# Arduino_NMEA_TestBoard.net
KiCad netlist of a schematic drawn in EAGLE
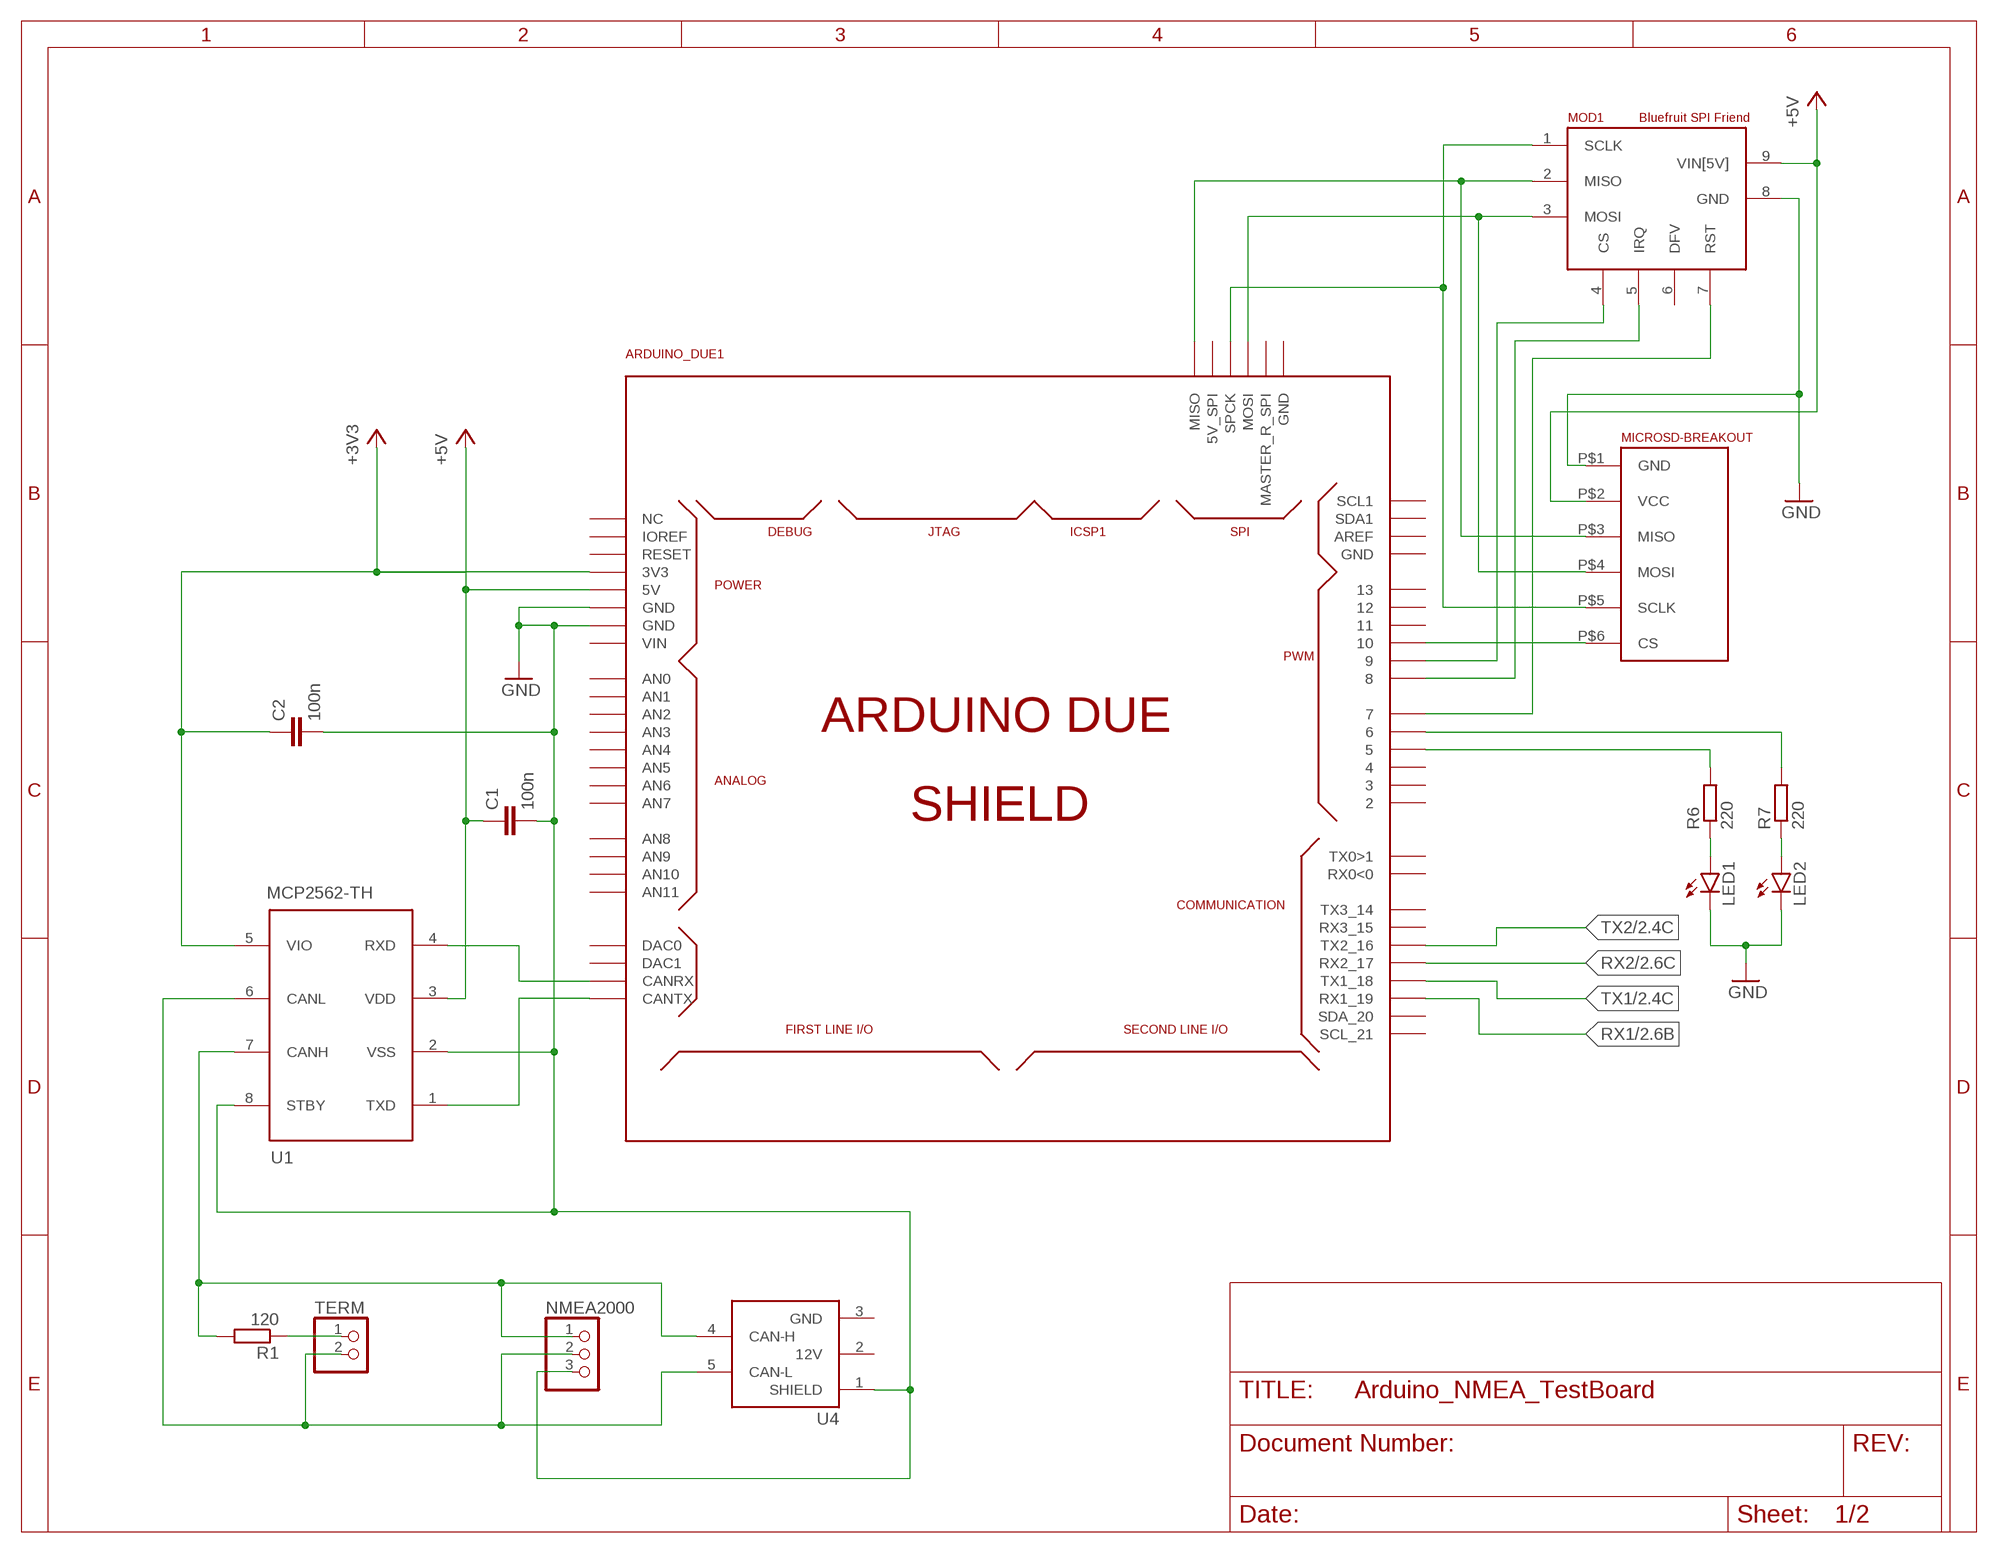
[diagram p0: schematic, sheet 1]
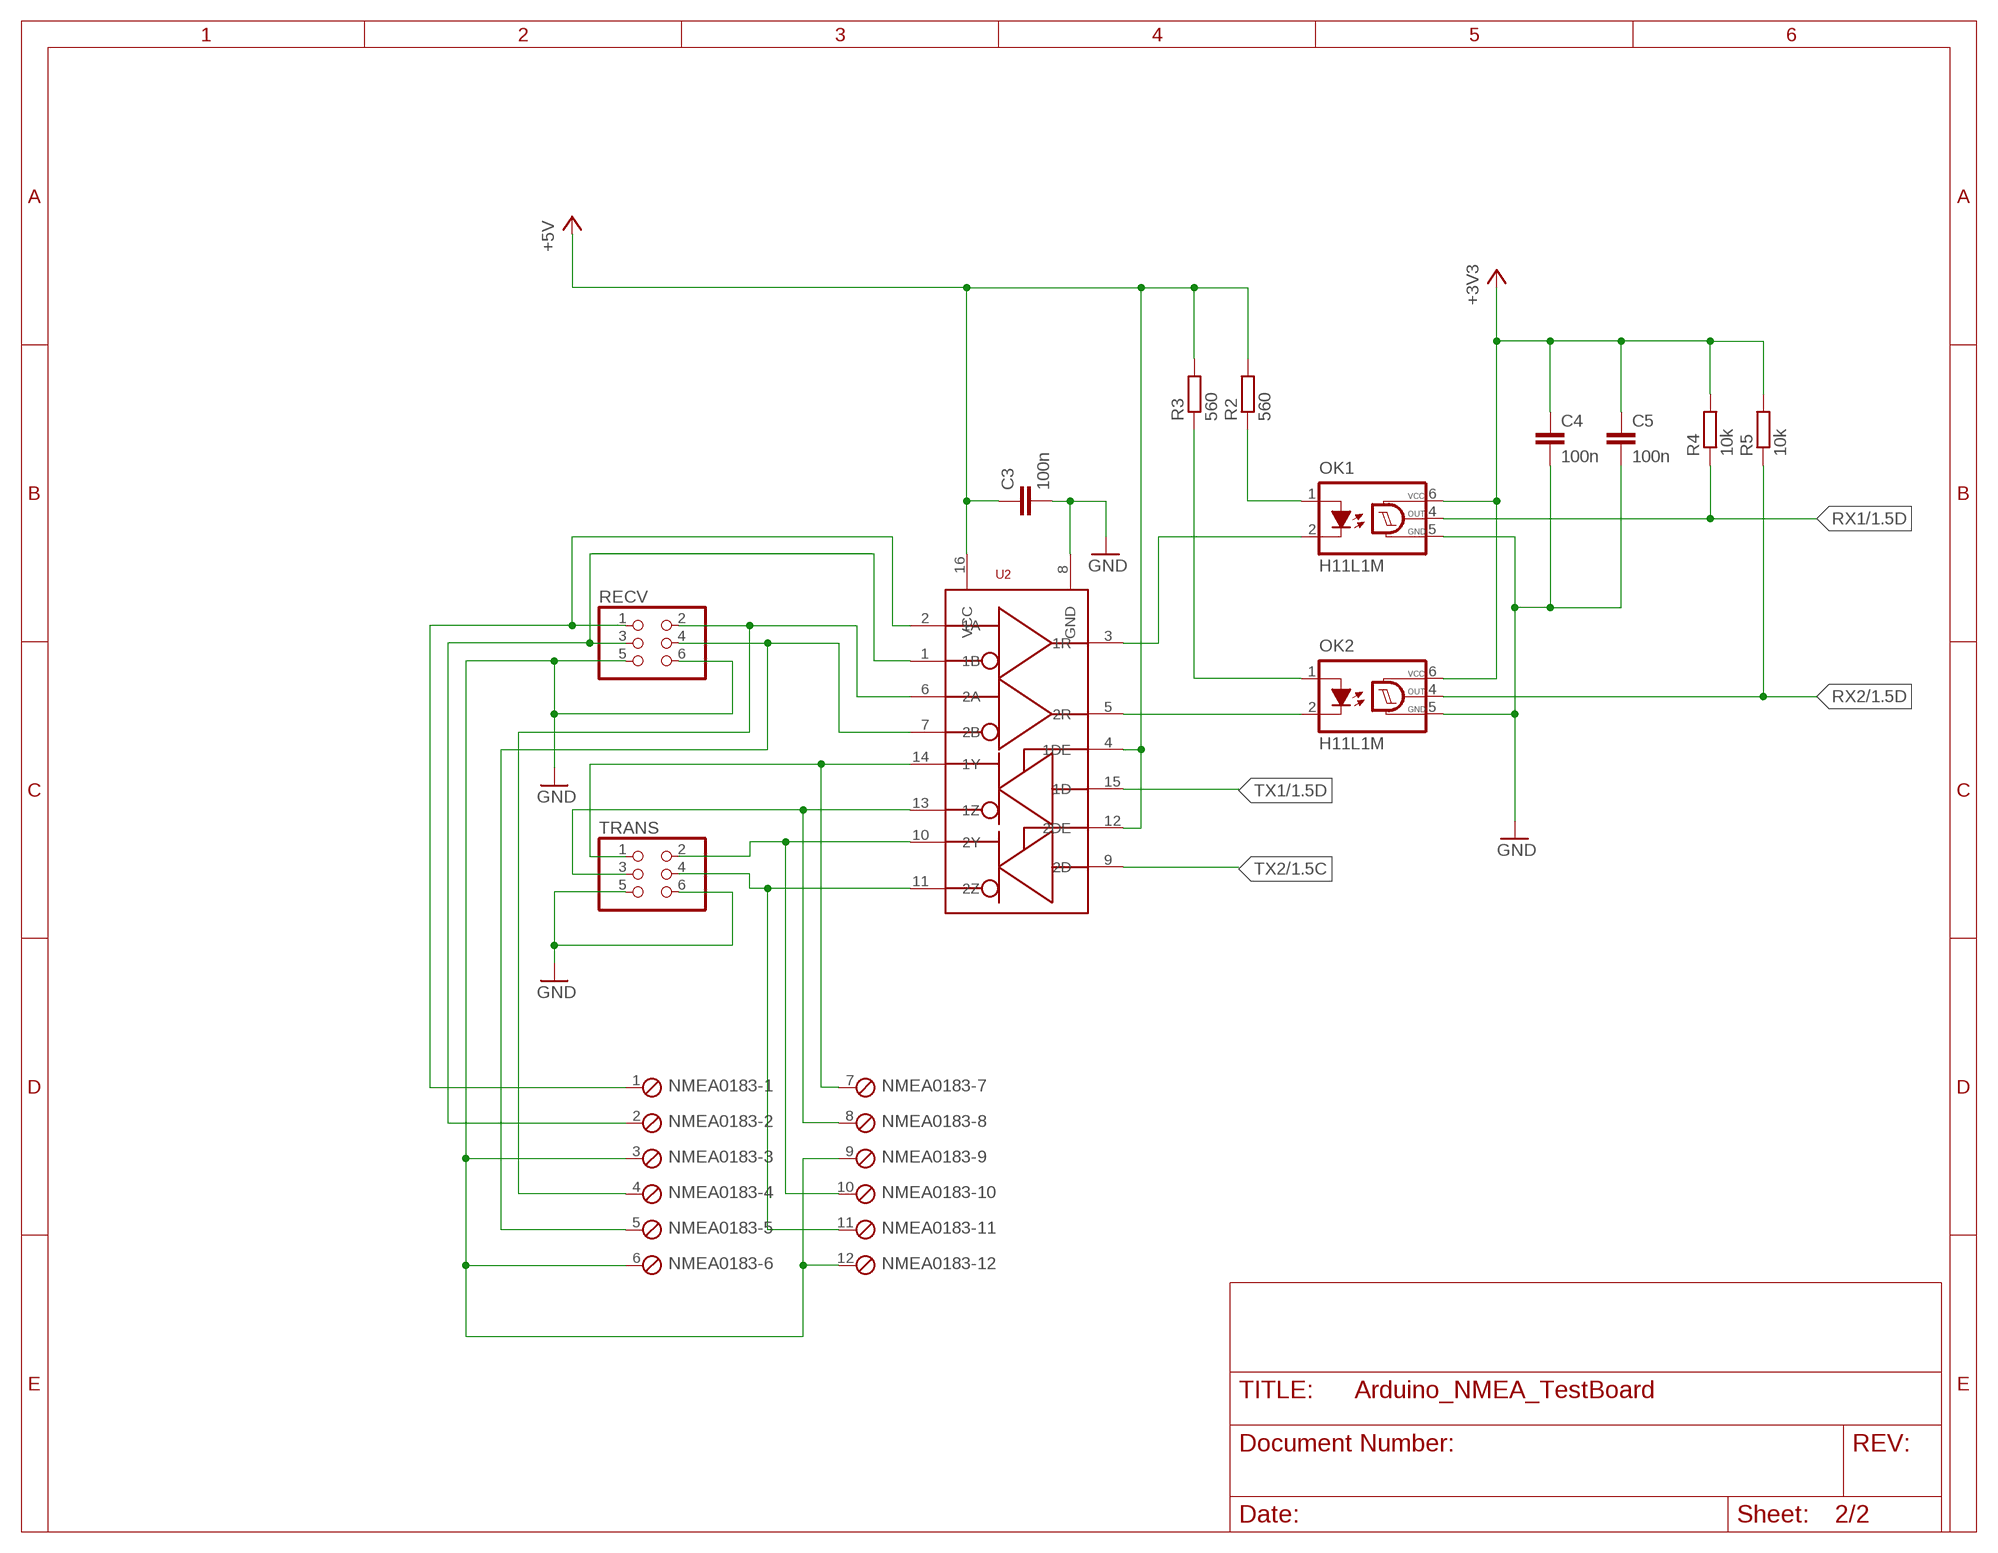
[diagram p1: schematic, sheet 2]

(export (version "E")
  (design (tool "Eeschema 10.0.6"))
  (components
    (comp (ref "C3")
      (value "100n")
      (footprint "eagle-import:C050-025X075")
      (libsource (lib "eagle-import") (part "C-EU050-025X075"))
    )
    (comp (ref "C4")
      (value "100n")
      (footprint "eagle-import:C050-025X075")
      (libsource (lib "eagle-import") (part "C-EU050-025X075"))
    )
    (comp (ref "C5")
      (value "100n")
      (footprint "eagle-import:C050-025X075")
      (libsource (lib "eagle-import") (part "C-EU050-025X075"))
    )
    (comp (ref "NMEA0183")
      (value "MPT12")
      (footprint "eagle-import:12POL254")
      (libsource (lib "eagle-import") (part "MPT12"))
    )
    (comp (ref "OK1")
      (value "H11L1M")
      (footprint "eagle-import:DIL06")
      (fields (field (name "MF") "FAIRCHILD SEMICONDUCTOR") (field (name "MPN") "H11L1-M"))
      (libsource (lib "eagle-import") (part "H11LM1"))
    )
    (comp (ref "OK2")
      (value "H11L1M")
      (footprint "eagle-import:DIL06")
      (fields (field (name "MF") "FAIRCHILD SEMICONDUCTOR") (field (name "MPN") "H11L1-M"))
      (libsource (lib "eagle-import") (part "H11LM1"))
    )
    (comp (ref "R2")
      (value "560")
      (footprint "eagle-import:0207_10")
      (libsource (lib "eagle-import") (part "R-EU_0207/10"))
    )
    (comp (ref "R3")
      (value "560")
      (footprint "eagle-import:0207_10")
      (libsource (lib "eagle-import") (part "R-EU_0207/10"))
    )
    (comp (ref "R4")
      (value "10k")
      (footprint "eagle-import:0207_10")
      (libsource (lib "eagle-import") (part "R-EU_0207/10"))
    )
    (comp (ref "R5")
      (value "10k")
      (footprint "eagle-import:0207_10")
      (libsource (lib "eagle-import") (part "R-EU_0207/10"))
    )
    (comp (ref "RECV")
      (value "PINHD-2X3")
      (footprint "eagle-import:2X03")
      (libsource (lib "eagle-import") (part "PINHD-2X3"))
    )
    (comp (ref "TRANS")
      (value "PINHD-2X3")
      (footprint "eagle-import:2X03")
      (libsource (lib "eagle-import") (part "PINHD-2X3"))
    )
    (comp (ref "U2")
      (value "SN65C1168")
      (footprint "eagle-import:DIP16")
      (libsource (lib "eagle-import") (part "SN65C1168"))
    )
    (comp (ref "ARDUINO_DUE1")
      (value "ARDUINO_DUE_SHIELD")
      (footprint "eagle-import:ARDUINO_DUE_SHIELD")
      (libsource (lib "eagle-import") (part "ARDUINO_DUE_SHIELD"))
    )
    (comp (ref "C1")
      (value "100n")
      (footprint "eagle-import:C050-025X075")
      (libsource (lib "eagle-import") (part "C-EU050-025X075"))
    )
    (comp (ref "C2")
      (value "100n")
      (footprint "eagle-import:C050-025X075")
      (libsource (lib "eagle-import") (part "C-EU050-025X075"))
    )
    (comp (ref "LED1")
      (value "LED5MM")
      (footprint "eagle-import:LED5MM")
      (libsource (lib "eagle-import") (part "LED5MM"))
    )
    (comp (ref "LED2")
      (value "LED5MM")
      (footprint "eagle-import:LED5MM")
      (libsource (lib "eagle-import") (part "LED5MM"))
    )
    (comp (ref "MICROSD-BREAKOUT")
      (value "MICROSD-BREAKOUT")
      (footprint "eagle-import:MICROSD-BREAKOUT")
      (libsource (lib "eagle-import") (part "MICROSD-BREAKOUT"))
    )
    (comp (ref "MOD1")
      (value "BLUEFRUIT-SPI-FRIEND")
      (footprint "eagle-import:BLE_SPIFRIEND")
      (libsource (lib "eagle-import") (part "BLUEFRUIT-SPI-FRIEND"))
    )
    (comp (ref "NMEA2000")
      (value "PINHD-1X3")
      (footprint "eagle-import:1X03")
      (libsource (lib "eagle-import") (part "PINHD-1X3"))
    )
    (comp (ref "R1")
      (value "120")
      (footprint "eagle-import:0207_10")
      (libsource (lib "eagle-import") (part "R-EU_0207/10"))
    )
    (comp (ref "R6")
      (value "220")
      (footprint "eagle-import:0207_10")
      (libsource (lib "eagle-import") (part "R-EU_0207/10"))
    )
    (comp (ref "R7")
      (value "220")
      (footprint "eagle-import:0207_10")
      (libsource (lib "eagle-import") (part "R-EU_0207/10"))
    )
    (comp (ref "TERM")
      (value "PINHD-1X2")
      (footprint "eagle-import:1X02")
      (libsource (lib "eagle-import") (part "PINHD-1X2"))
    )
    (comp (ref "U1")
      (value "MCP2562-TH")
      (footprint "eagle-import:DIP8")
      (libsource (lib "eagle-import") (part "MCP2562-TH"))
    )
    (comp (ref "U4")
      (value "NMEA2000-TOPSIDE")
      (footprint "eagle-import:NMEA2000-TOPSIDE")
      (libsource (lib "eagle-import") (part "NMEA2000-TOPSIDE"))
    )
  )
  (nets
    (net (code "1") (name "+3V3") (class "Default")
      (node (ref "ARDUINO_DUE1") (pin "3V3") (pinfunction "3V3_3V3") (pintype "bidirectional"))
      (node (ref "C2") (pin "1") (pinfunction "1_1") (pintype "passive"))
      (node (ref "C4") (pin "1") (pinfunction "1_1") (pintype "passive"))
      (node (ref "C5") (pin "1") (pinfunction "1_1") (pintype "passive"))
      (node (ref "OK1") (pin "6") (pinfunction "VCC_6") (pintype "power_in"))
      (node (ref "OK2") (pin "6") (pinfunction "VCC_6") (pintype "power_in"))
      (node (ref "R4") (pin "2") (pinfunction "2_2") (pintype "passive"))
      (node (ref "R5") (pin "2") (pinfunction "2_2") (pintype "passive"))
      (node (ref "U1") (pin "5") (pinfunction "VIO_5") (pintype "bidirectional"))
    )
    (net (code "2") (name "+5V") (class "Default")
      (node (ref "ARDUINO_DUE1") (pin "5V0") (pinfunction "5V_5V0") (pintype "bidirectional"))
      (node (ref "C1") (pin "1") (pinfunction "1_1") (pintype "passive"))
      (node (ref "C3") (pin "1") (pinfunction "1_1") (pintype "passive"))
      (node (ref "MICROSD-BREAKOUT") (pin "P$2") (pinfunction "VCC_P$2") (pintype "bidirectional"))
      (node (ref "MOD1") (pin "9") (pinfunction "VIN[5V]_9") (pintype "bidirectional"))
      (node (ref "R2") (pin "2") (pinfunction "2_2") (pintype "passive"))
      (node (ref "R3") (pin "2") (pinfunction "2_2") (pintype "passive"))
      (node (ref "U1") (pin "3") (pinfunction "VDD_3") (pintype "bidirectional"))
      (node (ref "U2") (pin "12") (pinfunction "2DE_12") (pintype "bidirectional"))
      (node (ref "U2") (pin "16") (pinfunction "VCC_16") (pintype "bidirectional"))
      (node (ref "U2") (pin "4") (pinfunction "1DE_4") (pintype "bidirectional"))
    )
    (net (code "3") (name "GND") (class "Default")
      (node (ref "ARDUINO_DUE1") (pin "GND") (pinfunction "GND_GND") (pintype "bidirectional"))
      (node (ref "ARDUINO_DUE1") (pin "GND_1") (pinfunction "GND_GND_1") (pintype "bidirectional"))
      (node (ref "C1") (pin "2") (pinfunction "2_2") (pintype "passive"))
      (node (ref "C2") (pin "2") (pinfunction "2_2") (pintype "passive"))
      (node (ref "C3") (pin "2") (pinfunction "2_2") (pintype "passive"))
      (node (ref "C4") (pin "2") (pinfunction "2_2") (pintype "passive"))
      (node (ref "C5") (pin "2") (pinfunction "2_2") (pintype "passive"))
      (node (ref "LED1") (pin "K") (pinfunction "C_K") (pintype "passive"))
      (node (ref "LED2") (pin "K") (pinfunction "C_K") (pintype "passive"))
      (node (ref "MICROSD-BREAKOUT") (pin "P$1") (pinfunction "GND_P$1") (pintype "bidirectional"))
      (node (ref "MOD1") (pin "8") (pinfunction "GND_8") (pintype "bidirectional"))
      (node (ref "NMEA0183") (pin "12") (pinfunction "1_12") (pintype "passive"))
      (node (ref "NMEA0183") (pin "3") (pinfunction "1_3") (pintype "passive"))
      (node (ref "NMEA0183") (pin "6") (pinfunction "1_6") (pintype "passive"))
      (node (ref "NMEA0183") (pin "9") (pinfunction "1_9") (pintype "passive"))
      (node (ref "NMEA2000") (pin "3") (pinfunction "3_3") (pintype "passive"))
      (node (ref "OK1") (pin "5") (pinfunction "GND_5") (pintype "power_in"))
      (node (ref "OK2") (pin "5") (pinfunction "GND_5") (pintype "power_in"))
      (node (ref "RECV") (pin "5") (pinfunction "5_5") (pintype "passive"))
      (node (ref "RECV") (pin "6") (pinfunction "6_6") (pintype "passive"))
      (node (ref "TRANS") (pin "5") (pinfunction "5_5") (pintype "passive"))
      (node (ref "TRANS") (pin "6") (pinfunction "6_6") (pintype "passive"))
      (node (ref "U1") (pin "2") (pinfunction "VSS_2") (pintype "bidirectional"))
      (node (ref "U1") (pin "8") (pinfunction "STBY_8") (pintype "bidirectional"))
      (node (ref "U2") (pin "8") (pinfunction "GND_8") (pintype "bidirectional"))
      (node (ref "U4") (pin "1") (pinfunction "SHIELD_1") (pintype "bidirectional"))
    )
    (net (code "4") (name "Net-(ARDUINO_DUE1-Pad5)") (class "Default")
      (node (ref "ARDUINO_DUE1") (pin "5") (pinfunction "5_5") (pintype "bidirectional"))
      (node (ref "R6") (pin "2") (pinfunction "2_2") (pintype "passive"))
    )
    (net (code "5") (name "Net-(ARDUINO_DUE1-Pad6)") (class "Default")
      (node (ref "ARDUINO_DUE1") (pin "6") (pinfunction "6_6") (pintype "bidirectional"))
      (node (ref "R7") (pin "2") (pinfunction "2_2") (pintype "passive"))
    )
    (net (code "6") (name "Net-(LED1-PadA)") (class "Default")
      (node (ref "LED1") (pin "A") (pinfunction "A_A") (pintype "passive"))
      (node (ref "R6") (pin "1") (pinfunction "1_1") (pintype "passive"))
    )
    (net (code "7") (name "Net-(LED2-PadA)") (class "Default")
      (node (ref "LED2") (pin "A") (pinfunction "A_A") (pintype "passive"))
      (node (ref "R7") (pin "1") (pinfunction "1_1") (pintype "passive"))
    )
    (net (code "8") (name "Net-(MICROSD-BREAKOUT-CS)") (class "Default")
      (node (ref "ARDUINO_DUE1") (pin "10") (pinfunction "10_10") (pintype "bidirectional"))
      (node (ref "MICROSD-BREAKOUT") (pin "P$6") (pinfunction "CS_P$6") (pintype "bidirectional"))
    )
    (net (code "9") (name "Net-(MICROSD-BREAKOUT-MISO)") (class "Default")
      (node (ref "ARDUINO_DUE1") (pin "MISO") (pinfunction "MISO_MISO") (pintype "bidirectional"))
      (node (ref "MICROSD-BREAKOUT") (pin "P$3") (pinfunction "MISO_P$3") (pintype "bidirectional"))
      (node (ref "MOD1") (pin "2") (pinfunction "MISO_2") (pintype "bidirectional"))
    )
    (net (code "10") (name "Net-(MICROSD-BREAKOUT-MOSI)") (class "Default")
      (node (ref "ARDUINO_DUE1") (pin "MOSI") (pinfunction "MOSI_MOSI") (pintype "bidirectional"))
      (node (ref "MICROSD-BREAKOUT") (pin "P$4") (pinfunction "MOSI_P$4") (pintype "bidirectional"))
      (node (ref "MOD1") (pin "3") (pinfunction "MOSI_3") (pintype "bidirectional"))
    )
    (net (code "11") (name "Net-(MICROSD-BREAKOUT-SCLK)") (class "Default")
      (node (ref "ARDUINO_DUE1") (pin "SPCK") (pinfunction "SPCK_SPCK") (pintype "bidirectional"))
      (node (ref "MICROSD-BREAKOUT") (pin "P$5") (pinfunction "SCLK_P$5") (pintype "bidirectional"))
      (node (ref "MOD1") (pin "1") (pinfunction "SCLK_1") (pintype "bidirectional"))
    )
    (net (code "12") (name "Net-(MOD1-CS)") (class "Default")
      (node (ref "ARDUINO_DUE1") (pin "9") (pinfunction "9_9") (pintype "bidirectional"))
      (node (ref "MOD1") (pin "4") (pinfunction "CS_4") (pintype "bidirectional"))
    )
    (net (code "13") (name "Net-(MOD1-IRQ)") (class "Default")
      (node (ref "ARDUINO_DUE1") (pin "8") (pinfunction "8_8") (pintype "bidirectional"))
      (node (ref "MOD1") (pin "5") (pinfunction "IRQ_5") (pintype "bidirectional"))
    )
    (net (code "14") (name "Net-(MOD1-RST)") (class "Default")
      (node (ref "ARDUINO_DUE1") (pin "7") (pinfunction "7_7") (pintype "bidirectional"))
      (node (ref "MOD1") (pin "7") (pinfunction "RST_7") (pintype "bidirectional"))
    )
    (net (code "15") (name "Net-(NMEA0183B-1)") (class "Default")
      (node (ref "NMEA0183") (pin "10") (pinfunction "1_10") (pintype "passive"))
      (node (ref "TRANS") (pin "2") (pinfunction "2_2") (pintype "passive"))
      (node (ref "U2") (pin "10") (pinfunction "2Y_10") (pintype "bidirectional"))
    )
    (net (code "16") (name "Net-(NMEA0183C-1)") (class "Default")
      (node (ref "NMEA0183") (pin "11") (pinfunction "1_11") (pintype "passive"))
      (node (ref "TRANS") (pin "4") (pinfunction "4_4") (pintype "passive"))
      (node (ref "U2") (pin "11") (pinfunction "2Z_11") (pintype "bidirectional"))
    )
    (net (code "17") (name "Net-(NMEA0183E-1)") (class "Default")
      (node (ref "NMEA0183") (pin "2") (pinfunction "1_2") (pintype "passive"))
      (node (ref "RECV") (pin "3") (pinfunction "3_3") (pintype "passive"))
      (node (ref "U2") (pin "1") (pinfunction "1B_1") (pintype "bidirectional"))
    )
    (net (code "18") (name "Net-(NMEA0183G-1)") (class "Default")
      (node (ref "NMEA0183") (pin "4") (pinfunction "1_4") (pintype "passive"))
      (node (ref "RECV") (pin "2") (pinfunction "2_2") (pintype "passive"))
      (node (ref "U2") (pin "6") (pinfunction "2A_6") (pintype "bidirectional"))
    )
    (net (code "19") (name "Net-(NMEA0183H-1)") (class "Default")
      (node (ref "NMEA0183") (pin "5") (pinfunction "1_5") (pintype "passive"))
      (node (ref "RECV") (pin "4") (pinfunction "4_4") (pintype "passive"))
      (node (ref "U2") (pin "7") (pinfunction "2B_7") (pintype "bidirectional"))
    )
    (net (code "20") (name "Net-(NMEA0183J-1)") (class "Default")
      (node (ref "NMEA0183") (pin "7") (pinfunction "1_7") (pintype "passive"))
      (node (ref "TRANS") (pin "1") (pinfunction "1_1") (pintype "passive"))
      (node (ref "U2") (pin "14") (pinfunction "1Y_14") (pintype "bidirectional"))
    )
    (net (code "21") (name "Net-(NMEA0183K-1)") (class "Default")
      (node (ref "NMEA0183") (pin "8") (pinfunction "1_8") (pintype "passive"))
      (node (ref "TRANS") (pin "3") (pinfunction "3_3") (pintype "passive"))
      (node (ref "U2") (pin "13") (pinfunction "1Z_13") (pintype "bidirectional"))
    )
    (net (code "22") (name "Net-(OK1-A)") (class "Default")
      (node (ref "OK1") (pin "1") (pinfunction "A_1") (pintype "passive"))
      (node (ref "R2") (pin "1") (pinfunction "1_1") (pintype "passive"))
    )
    (net (code "23") (name "Net-(OK1-C)") (class "Default")
      (node (ref "OK1") (pin "2") (pinfunction "C_2") (pintype "passive"))
      (node (ref "U2") (pin "3") (pinfunction "1R_3") (pintype "bidirectional"))
    )
    (net (code "24") (name "Net-(OK2-A)") (class "Default")
      (node (ref "OK2") (pin "1") (pinfunction "A_1") (pintype "passive"))
      (node (ref "R3") (pin "1") (pinfunction "1_1") (pintype "passive"))
    )
    (net (code "25") (name "Net-(OK2-C)") (class "Default")
      (node (ref "OK2") (pin "2") (pinfunction "C_2") (pintype "passive"))
      (node (ref "U2") (pin "5") (pinfunction "2R_5") (pintype "bidirectional"))
    )
    (net (code "26") (name "Net-(R1-Pad1)") (class "Default")
      (node (ref "R1") (pin "1") (pinfunction "1_1") (pintype "passive"))
      (node (ref "TERM") (pin "1") (pinfunction "1_1") (pintype "passive"))
    )
    (net (code "27") (name "Net-(U1-CANH)") (class "Default")
      (node (ref "NMEA2000") (pin "1") (pinfunction "1_1") (pintype "passive"))
      (node (ref "R1") (pin "2") (pinfunction "2_2") (pintype "passive"))
      (node (ref "U1") (pin "7") (pinfunction "CANH_7") (pintype "bidirectional"))
      (node (ref "U4") (pin "4") (pinfunction "CAN-H_4") (pintype "bidirectional"))
    )
    (net (code "28") (name "Net-(U1-CANL)") (class "Default")
      (node (ref "NMEA2000") (pin "2") (pinfunction "2_2") (pintype "passive"))
      (node (ref "TERM") (pin "2") (pinfunction "2_2") (pintype "passive"))
      (node (ref "U1") (pin "6") (pinfunction "CANL_6") (pintype "bidirectional"))
      (node (ref "U4") (pin "5") (pinfunction "CAN-L_5") (pintype "bidirectional"))
    )
    (net (code "29") (name "Net-(U1-RXD)") (class "Default")
      (node (ref "ARDUINO_DUE1") (pin "CANRX") (pinfunction "CANRX_CANRX") (pintype "bidirectional"))
      (node (ref "U1") (pin "4") (pinfunction "RXD_4") (pintype "bidirectional"))
    )
    (net (code "30") (name "Net-(U1-TXD)") (class "Default")
      (node (ref "ARDUINO_DUE1") (pin "CANTX") (pinfunction "CANTX_CANTX") (pintype "bidirectional"))
      (node (ref "U1") (pin "1") (pinfunction "TXD_1") (pintype "bidirectional"))
    )
    (net (code "31") (name "Net-(U2-1A)") (class "Default")
      (node (ref "NMEA0183") (pin "1") (pinfunction "1_1") (pintype "passive"))
      (node (ref "RECV") (pin "1") (pinfunction "1_1") (pintype "passive"))
      (node (ref "U2") (pin "2") (pinfunction "1A_2") (pintype "bidirectional"))
    )
    (net (code "32") (name "RX1") (class "Default")
      (node (ref "ARDUINO_DUE1") (pin "19") (pinfunction "RX1_19_19") (pintype "bidirectional"))
      (node (ref "OK1") (pin "4") (pinfunction "OUT_4") (pintype "output"))
      (node (ref "R4") (pin "1") (pinfunction "1_1") (pintype "passive"))
    )
    (net (code "33") (name "RX2") (class "Default")
      (node (ref "ARDUINO_DUE1") (pin "17") (pinfunction "RX2_17_17") (pintype "bidirectional"))
      (node (ref "OK2") (pin "4") (pinfunction "OUT_4") (pintype "output"))
      (node (ref "R5") (pin "1") (pinfunction "1_1") (pintype "passive"))
    )
    (net (code "34") (name "TX1") (class "Default")
      (node (ref "ARDUINO_DUE1") (pin "18") (pinfunction "TX1_18_18") (pintype "bidirectional"))
      (node (ref "U2") (pin "15") (pinfunction "1D_15") (pintype "bidirectional"))
    )
    (net (code "35") (name "TX2") (class "Default")
      (node (ref "ARDUINO_DUE1") (pin "16") (pinfunction "TX2_16_16") (pintype "bidirectional"))
      (node (ref "U2") (pin "9") (pinfunction "2D_9") (pintype "bidirectional"))
    )
    (net (code "36") (name "unconnected-(ARDUINO_DUE1-5V_SPI-Pad5V_2)") (class "Default")
      (node (ref "ARDUINO_DUE1") (pin "5V_2") (pinfunction "5V_SPI_5V_2") (pintype "bidirectional"))
    )
    (net (code "37") (name "unconnected-(ARDUINO_DUE1-AN0-PadA0)") (class "Default")
      (node (ref "ARDUINO_DUE1") (pin "A0") (pinfunction "AN0_A0") (pintype "bidirectional"))
    )
    (net (code "38") (name "unconnected-(ARDUINO_DUE1-AN1-PadA1)") (class "Default")
      (node (ref "ARDUINO_DUE1") (pin "A1") (pinfunction "AN1_A1") (pintype "bidirectional"))
    )
    (net (code "39") (name "unconnected-(ARDUINO_DUE1-AN2-PadA2)") (class "Default")
      (node (ref "ARDUINO_DUE1") (pin "A2") (pinfunction "AN2_A2") (pintype "bidirectional"))
    )
    (net (code "40") (name "unconnected-(ARDUINO_DUE1-AN3-PadA3)") (class "Default")
      (node (ref "ARDUINO_DUE1") (pin "A3") (pinfunction "AN3_A3") (pintype "bidirectional"))
    )
    (net (code "41") (name "unconnected-(ARDUINO_DUE1-AN4-PadA4)") (class "Default")
      (node (ref "ARDUINO_DUE1") (pin "A4") (pinfunction "AN4_A4") (pintype "bidirectional"))
    )
    (net (code "42") (name "unconnected-(ARDUINO_DUE1-AN5-PadA5)") (class "Default")
      (node (ref "ARDUINO_DUE1") (pin "A5") (pinfunction "AN5_A5") (pintype "bidirectional"))
    )
    (net (code "43") (name "unconnected-(ARDUINO_DUE1-AN6-PadA6)") (class "Default")
      (node (ref "ARDUINO_DUE1") (pin "A6") (pinfunction "AN6_A6") (pintype "bidirectional"))
    )
    (net (code "44") (name "unconnected-(ARDUINO_DUE1-AN7-PadA7)") (class "Default")
      (node (ref "ARDUINO_DUE1") (pin "A7") (pinfunction "AN7_A7") (pintype "bidirectional"))
    )
    (net (code "45") (name "unconnected-(ARDUINO_DUE1-AN8-PadA8)") (class "Default")
      (node (ref "ARDUINO_DUE1") (pin "A8") (pinfunction "AN8_A8") (pintype "bidirectional"))
    )
    (net (code "46") (name "unconnected-(ARDUINO_DUE1-AN9-PadA9)") (class "Default")
      (node (ref "ARDUINO_DUE1") (pin "A9") (pinfunction "AN9_A9") (pintype "bidirectional"))
    )
    (net (code "47") (name "unconnected-(ARDUINO_DUE1-AN10-PadA10)") (class "Default")
      (node (ref "ARDUINO_DUE1") (pin "A10") (pinfunction "AN10_A10") (pintype "bidirectional"))
    )
    (net (code "48") (name "unconnected-(ARDUINO_DUE1-AN11-PadA11)") (class "Default")
      (node (ref "ARDUINO_DUE1") (pin "A11") (pinfunction "AN11_A11") (pintype "bidirectional"))
    )
    (net (code "49") (name "unconnected-(ARDUINO_DUE1-GND-PadGND_4)") (class "Default")
      (node (ref "ARDUINO_DUE1") (pin "GND_4") (pinfunction "GND_GND_4") (pintype "bidirectional"))
    )
    (net (code "50") (name "unconnected-(ARDUINO_DUE1-GND-PadGND_5)") (class "Default")
      (node (ref "ARDUINO_DUE1") (pin "GND_5") (pinfunction "GND_GND_5") (pintype "bidirectional"))
    )
    (net (code "51") (name "unconnected-(ARDUINO_DUE1-MASTER_R_SPI-PadMASTER_RESET_SPI)") (class "Default")
      (node (ref "ARDUINO_DUE1") (pin "MASTER_RESET_SPI") (pinfunction "MASTER_R_SPI_MASTER_RESET_SPI") (pintype "bidirectional"))
    )
    (net (code "52") (name "unconnected-(ARDUINO_DUE1-NC-PadNC_2)") (class "Default")
      (node (ref "ARDUINO_DUE1") (pin "NC_2") (pinfunction "NC_NC_2") (pintype "no_connect"))
    )
    (net (code "53") (name "unconnected-(ARDUINO_DUE1-Pad2)") (class "Default")
      (node (ref "ARDUINO_DUE1") (pin "2") (pinfunction "2_2") (pintype "bidirectional"))
    )
    (net (code "54") (name "unconnected-(ARDUINO_DUE1-Pad3)") (class "Default")
      (node (ref "ARDUINO_DUE1") (pin "3") (pinfunction "3_3") (pintype "bidirectional"))
    )
    (net (code "55") (name "unconnected-(ARDUINO_DUE1-Pad4)") (class "Default")
      (node (ref "ARDUINO_DUE1") (pin "4") (pinfunction "4_4") (pintype "bidirectional"))
    )
    (net (code "56") (name "unconnected-(ARDUINO_DUE1-Pad11)") (class "Default")
      (node (ref "ARDUINO_DUE1") (pin "11") (pinfunction "11_11") (pintype "bidirectional"))
    )
    (net (code "57") (name "unconnected-(ARDUINO_DUE1-Pad12)") (class "Default")
      (node (ref "ARDUINO_DUE1") (pin "12") (pinfunction "12_12") (pintype "bidirectional"))
    )
    (net (code "58") (name "unconnected-(ARDUINO_DUE1-Pad13)") (class "Default")
      (node (ref "ARDUINO_DUE1") (pin "13") (pinfunction "13_13") (pintype "bidirectional"))
    )
    (net (code "59") (name "unconnected-(ARDUINO_DUE1-PadAREF)") (class "Default")
      (node (ref "ARDUINO_DUE1") (pin "AREF") (pinfunction "AREF_AREF") (pintype "bidirectional"))
    )
    (net (code "60") (name "unconnected-(ARDUINO_DUE1-PadDAC0)") (class "Default")
      (node (ref "ARDUINO_DUE1") (pin "DAC0") (pinfunction "DAC0_DAC0") (pintype "bidirectional"))
    )
    (net (code "61") (name "unconnected-(ARDUINO_DUE1-PadDAC1)") (class "Default")
      (node (ref "ARDUINO_DUE1") (pin "DAC1") (pinfunction "DAC1_DAC1") (pintype "bidirectional"))
    )
    (net (code "62") (name "unconnected-(ARDUINO_DUE1-PadIOREF)") (class "Default")
      (node (ref "ARDUINO_DUE1") (pin "IOREF") (pinfunction "IOREF_IOREF") (pintype "bidirectional"))
    )
    (net (code "63") (name "unconnected-(ARDUINO_DUE1-PadRESET)") (class "Default")
      (node (ref "ARDUINO_DUE1") (pin "RESET") (pinfunction "RESET_RESET") (pintype "bidirectional"))
    )
    (net (code "64") (name "unconnected-(ARDUINO_DUE1-PadSCL1)") (class "Default")
      (node (ref "ARDUINO_DUE1") (pin "SCL1") (pinfunction "SCL1_SCL1") (pintype "bidirectional"))
    )
    (net (code "65") (name "unconnected-(ARDUINO_DUE1-PadSDA1)") (class "Default")
      (node (ref "ARDUINO_DUE1") (pin "SDA1") (pinfunction "SDA1_SDA1") (pintype "bidirectional"))
    )
    (net (code "66") (name "unconnected-(ARDUINO_DUE1-PadVIN)") (class "Default")
      (node (ref "ARDUINO_DUE1") (pin "VIN") (pinfunction "VIN_VIN") (pintype "bidirectional"))
    )
    (net (code "67") (name "unconnected-(ARDUINO_DUE1-RX0<0-Pad0)") (class "Default")
      (node (ref "ARDUINO_DUE1") (pin "0") (pinfunction "RX0<0_0") (pintype "bidirectional"))
    )
    (net (code "68") (name "unconnected-(ARDUINO_DUE1-RX3_15-Pad15)") (class "Default")
      (node (ref "ARDUINO_DUE1") (pin "15") (pinfunction "RX3_15_15") (pintype "bidirectional"))
    )
    (net (code "69") (name "unconnected-(ARDUINO_DUE1-SCL_21-Pad21)") (class "Default")
      (node (ref "ARDUINO_DUE1") (pin "21") (pinfunction "SCL_21_21") (pintype "bidirectional"))
    )
    (net (code "70") (name "unconnected-(ARDUINO_DUE1-SDA_20-Pad20)") (class "Default")
      (node (ref "ARDUINO_DUE1") (pin "20") (pinfunction "SDA_20_20") (pintype "bidirectional"))
    )
    (net (code "71") (name "unconnected-(ARDUINO_DUE1-TX0>1-Pad1)") (class "Default")
      (node (ref "ARDUINO_DUE1") (pin "1") (pinfunction "TX0>1_1") (pintype "bidirectional"))
    )
    (net (code "72") (name "unconnected-(ARDUINO_DUE1-TX3_14-Pad14)") (class "Default")
      (node (ref "ARDUINO_DUE1") (pin "14") (pinfunction "TX3_14_14") (pintype "bidirectional"))
    )
    (net (code "73") (name "unconnected-(MOD1-DFV-Pad6)") (class "Default")
      (node (ref "MOD1") (pin "6") (pinfunction "DFV_6") (pintype "bidirectional"))
    )
    (net (code "74") (name "unconnected-(U4-12V-Pad2)") (class "Default")
      (node (ref "U4") (pin "2") (pinfunction "12V_2") (pintype "bidirectional"))
    )
    (net (code "75") (name "unconnected-(U4-GND-Pad3)") (class "Default")
      (node (ref "U4") (pin "3") (pinfunction "GND_3") (pintype "bidirectional"))
    )
  )
)
